# Sensor_Plug_PCB.net
KiCad netlist of a schematic drawn in EAGLE
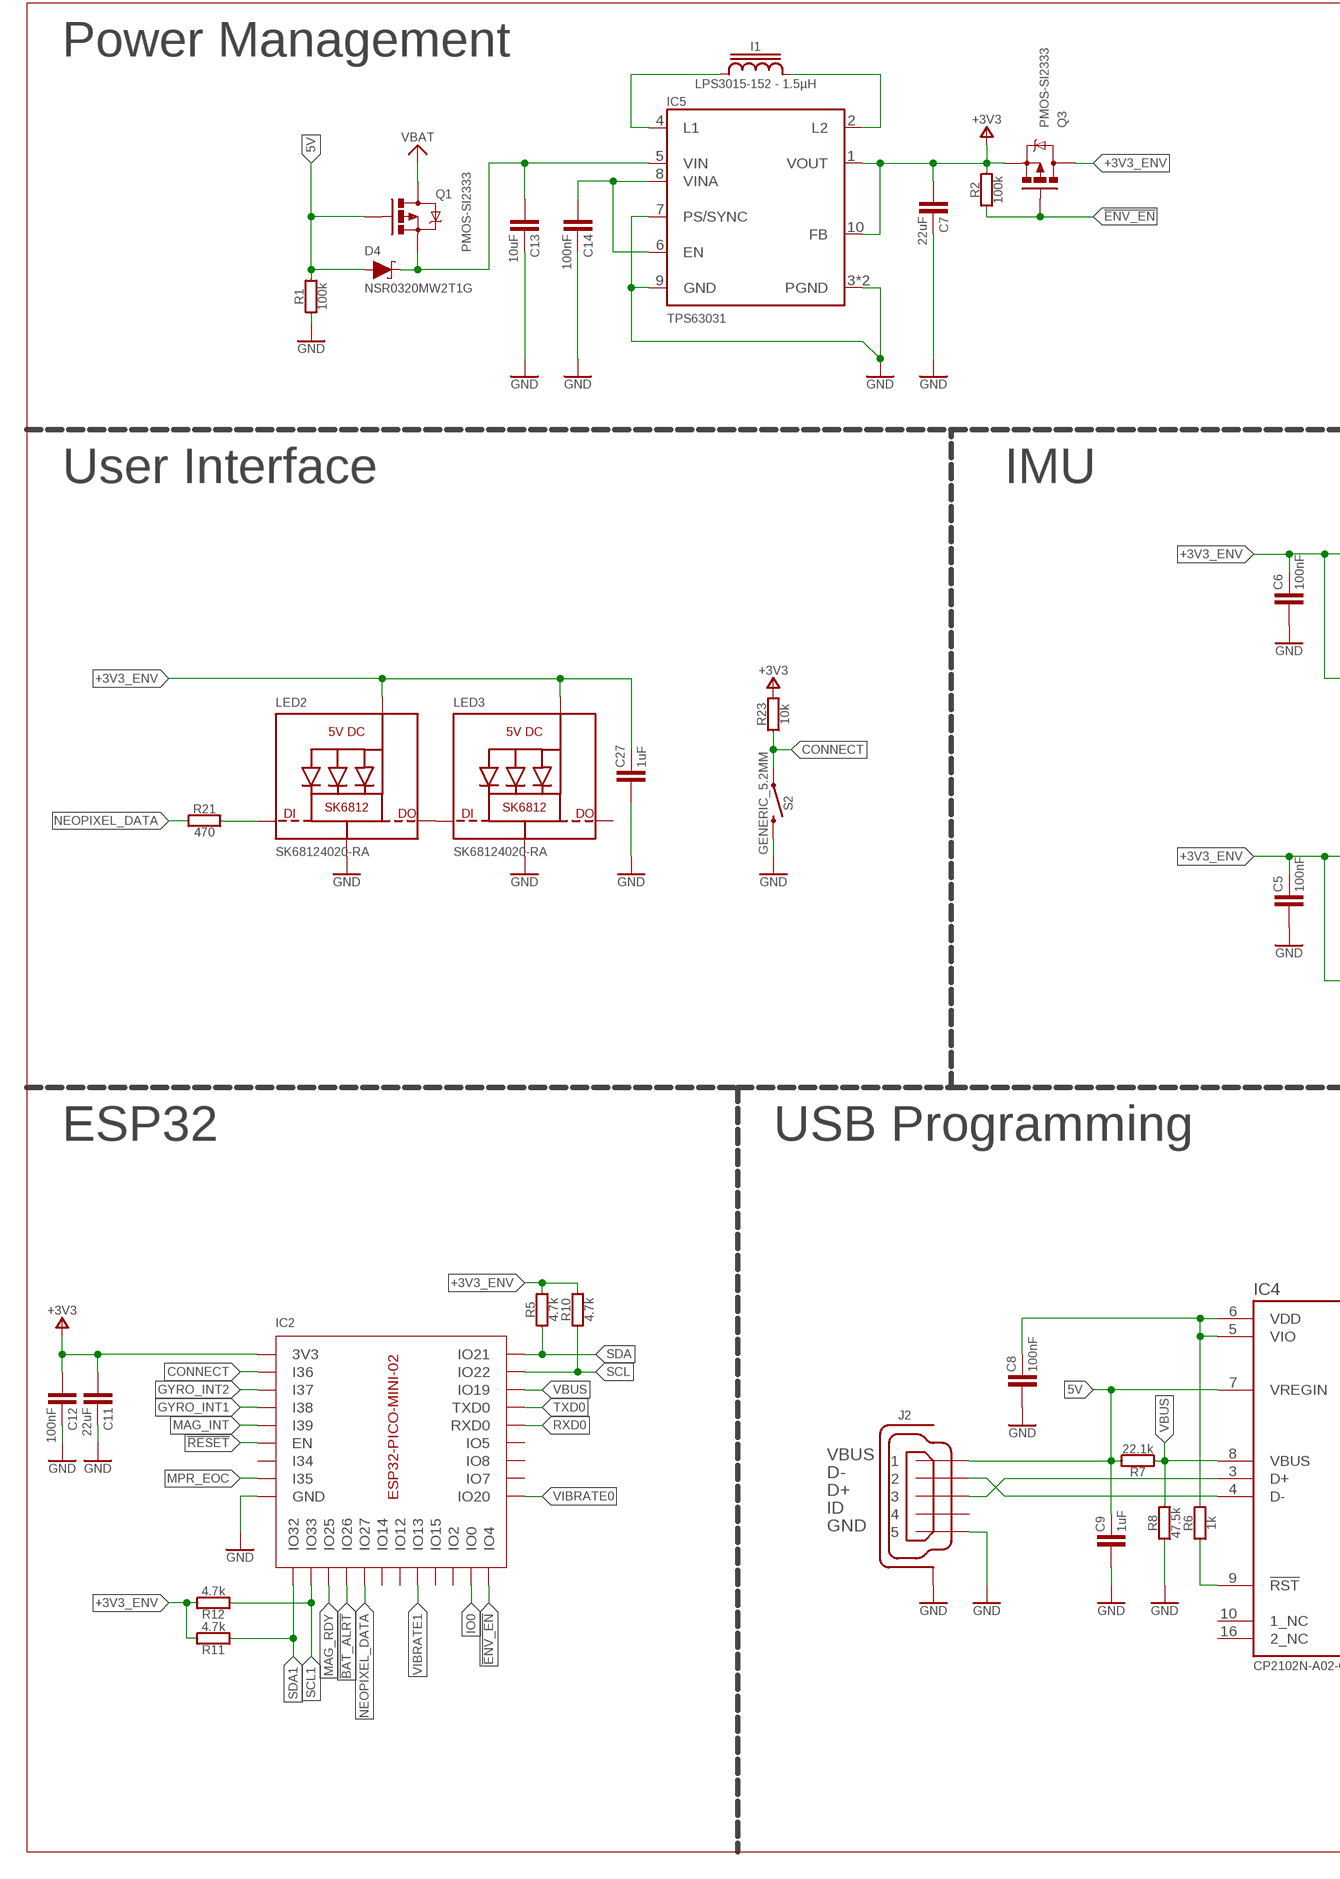
[diagram p0: schematic, sheet 1, part 1 of 2]
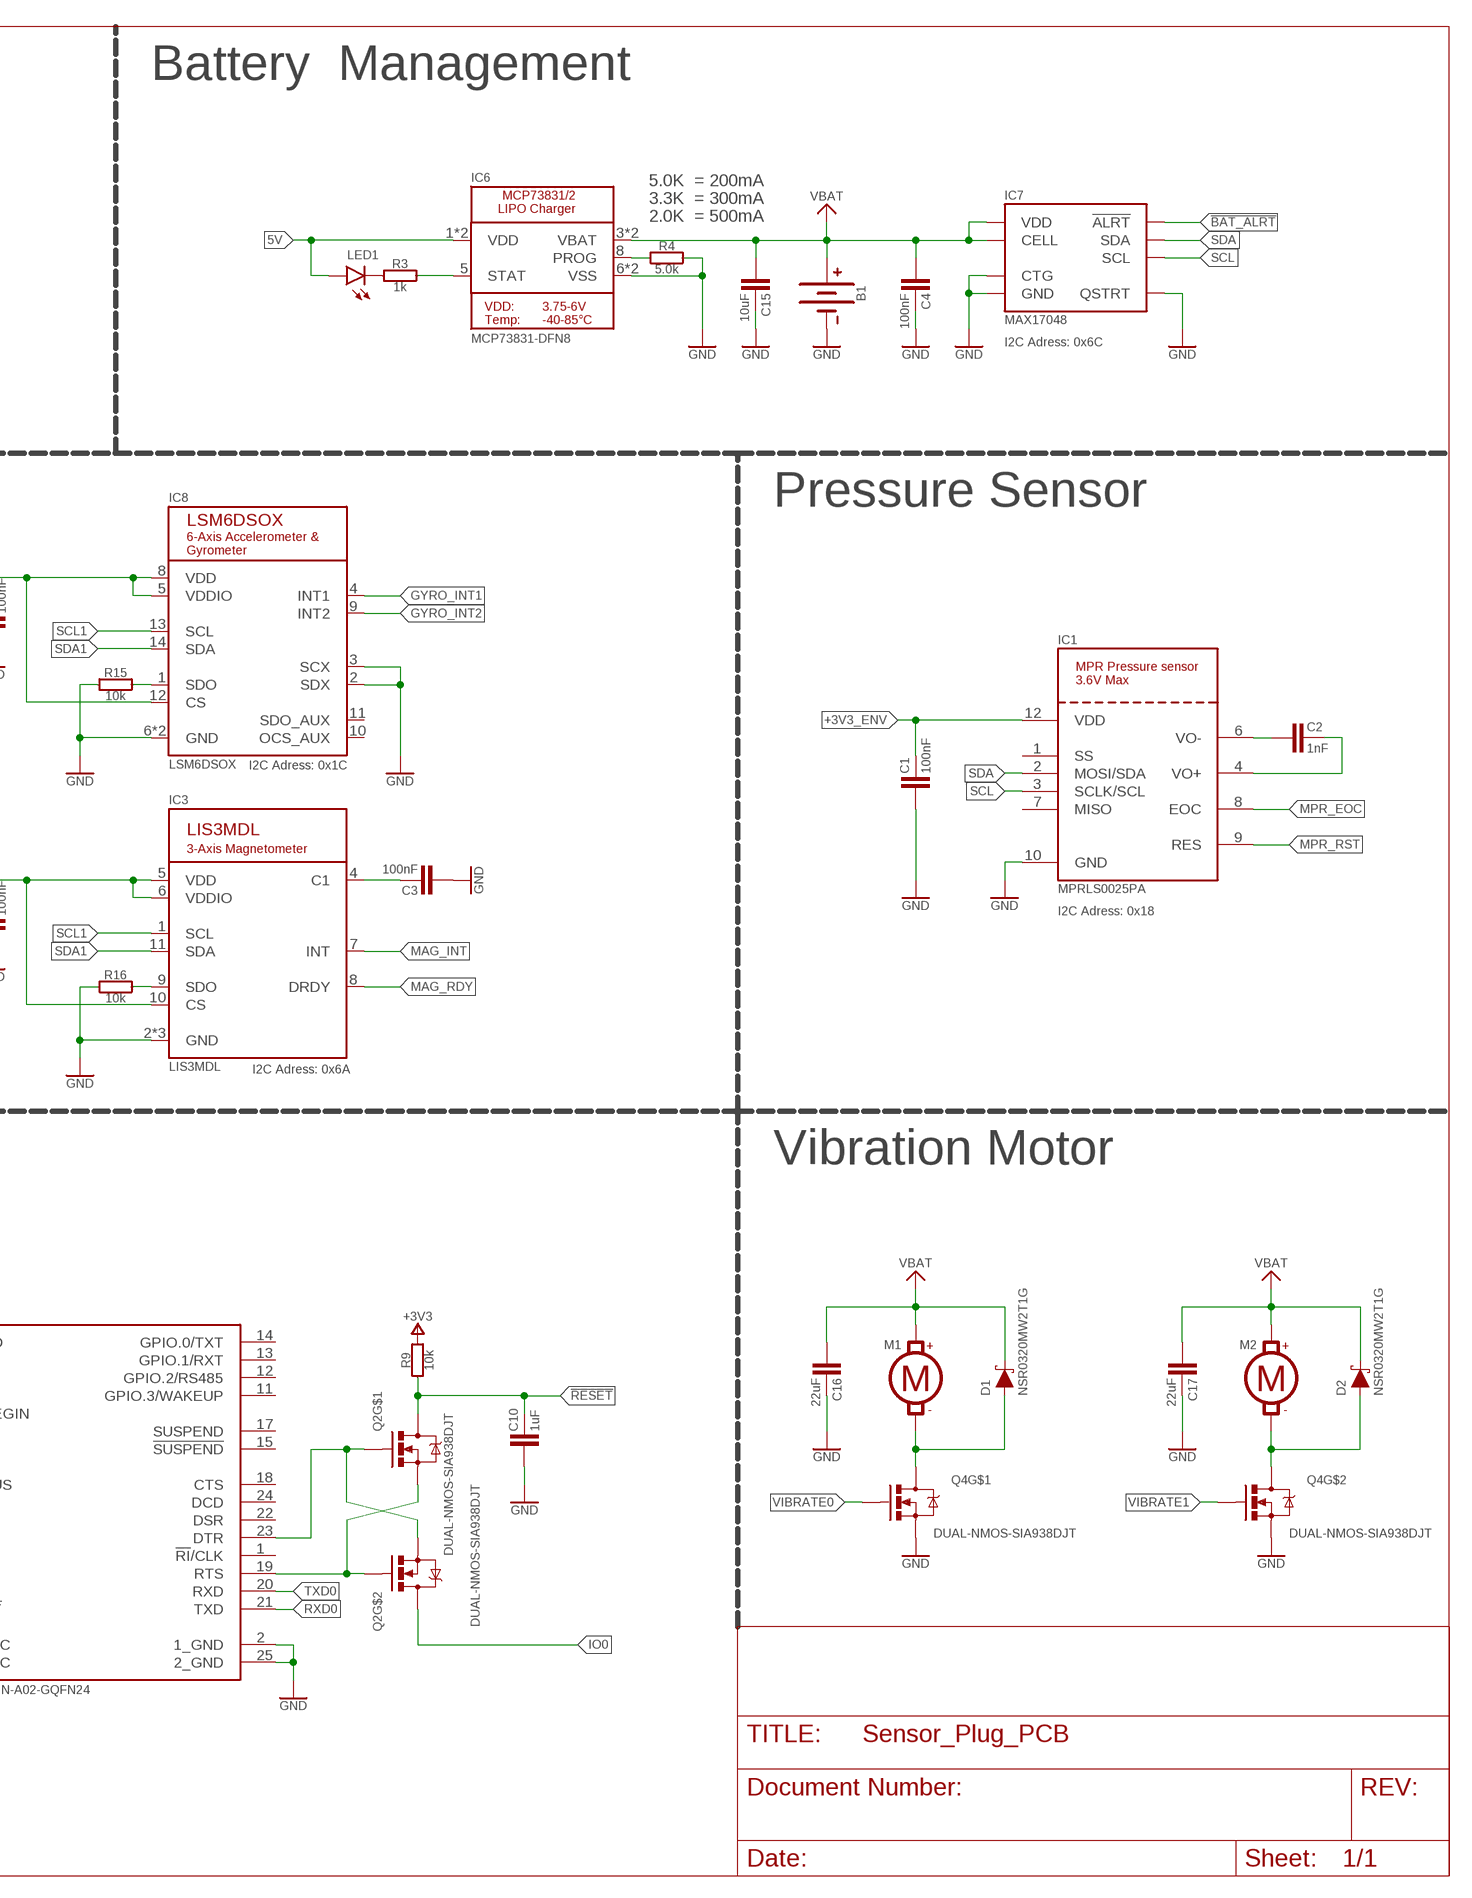
[diagram p1: schematic, sheet 1, part 2 of 2]

(export (version "E")
  (design (tool "Eeschema 10.0.6"))
  (components
    (comp (ref "B1")
      (value "LIPO-JST_PH_SMDV-02")
      (footprint "eagle-import:JST_PH_SMDV-02")
      (libsource (lib "eagle-import") (part "LIPO-JST_PH_SMDV-02"))
    )
    (comp (ref "C1")
      (value "100nF")
      (footprint "eagle-import:C0603")
      (libsource (lib "eagle-import") (part "C-0603"))
    )
    (comp (ref "C2")
      (value "1nF")
      (footprint "eagle-import:C0603")
      (libsource (lib "eagle-import") (part "C-0603"))
    )
    (comp (ref "C3")
      (value "100nF")
      (footprint "eagle-import:C0603")
      (libsource (lib "eagle-import") (part "C-0603"))
    )
    (comp (ref "C4")
      (value "100nF")
      (footprint "eagle-import:C0603")
      (libsource (lib "eagle-import") (part "C-0603"))
    )
    (comp (ref "C5")
      (value "100nF")
      (footprint "eagle-import:C0603")
      (libsource (lib "eagle-import") (part "C-0603"))
    )
    (comp (ref "C6")
      (value "100nF")
      (footprint "eagle-import:C0603")
      (libsource (lib "eagle-import") (part "C-0603"))
    )
    (comp (ref "C7")
      (value "22uF")
      (footprint "eagle-import:C0805")
      (libsource (lib "eagle-import") (part "C-0805"))
    )
    (comp (ref "C8")
      (value "100nF")
      (footprint "eagle-import:C0603")
      (libsource (lib "eagle-import") (part "C-0603"))
    )
    (comp (ref "C9")
      (value "1uF")
      (footprint "eagle-import:C0603")
      (libsource (lib "eagle-import") (part "C-0603"))
    )
    (comp (ref "C10")
      (value "1uF")
      (footprint "eagle-import:C0603")
      (libsource (lib "eagle-import") (part "C-0603"))
    )
    (comp (ref "C11")
      (value "22uF")
      (footprint "eagle-import:C0805")
      (libsource (lib "eagle-import") (part "C-0805"))
    )
    (comp (ref "C12")
      (value "100nF")
      (footprint "eagle-import:C0603")
      (libsource (lib "eagle-import") (part "C-0603"))
    )
    (comp (ref "C13")
      (value "10uF")
      (footprint "eagle-import:C0805")
      (libsource (lib "eagle-import") (part "C-0805"))
    )
    (comp (ref "C14")
      (value "100nF")
      (footprint "eagle-import:C0603")
      (libsource (lib "eagle-import") (part "C-0603"))
    )
    (comp (ref "C15")
      (value "10uF")
      (footprint "eagle-import:C0805")
      (libsource (lib "eagle-import") (part "C-0805"))
    )
    (comp (ref "C16")
      (value "22uF")
      (footprint "eagle-import:C0805")
      (libsource (lib "eagle-import") (part "C-0805"))
    )
    (comp (ref "C17")
      (value "22uF")
      (footprint "eagle-import:C0805")
      (libsource (lib "eagle-import") (part "C-0805"))
    )
    (comp (ref "C27")
      (value "1uF")
      (footprint "eagle-import:C0603")
      (libsource (lib "eagle-import") (part "C-0603"))
    )
    (comp (ref "D1")
      (value "NSR0320MW2T1G")
      (footprint "eagle-import:SOD-323")
      (libsource (lib "eagle-import") (part "DIODE-SCHOTTKY-SOD323"))
    )
    (comp (ref "D2")
      (value "NSR0320MW2T1G")
      (footprint "eagle-import:SOD-323")
      (libsource (lib "eagle-import") (part "DIODE-SCHOTTKY-SOD323"))
    )
    (comp (ref "D4")
      (value "NSR0320MW2T1G")
      (footprint "eagle-import:SOD-323")
      (libsource (lib "eagle-import") (part "DIODE-SCHOTTKY-SOD323"))
    )
    (comp (ref "I1")
      (value "LPS3015-152 - 1.5µH")
      (footprint "eagle-import:LPS3015")
      (libsource (lib "eagle-import") (part "I-LPS3015"))
    )
    (comp (ref "IC1")
      (value "MPRLS0025PA")
      (footprint "eagle-import:MPRLS0025PA")
      (fields (field (name "MPN") "MPRLS0025PA00001A"))
      (libsource (lib "eagle-import") (part "MPRLS0025PA"))
    )
    (comp (ref "IC2")
      (value "EPS32-PICO-MINI-02")
      (footprint "eagle-import:ESP32-PICO-MINI-02")
      (libsource (lib "eagle-import") (part "EPS32-PICO-MINI-02"))
    )
    (comp (ref "IC3")
      (value "LIS3MDL")
      (footprint "eagle-import:LGA12_2X2MM")
      (libsource (lib "eagle-import") (part "LIS3MDL"))
    )
    (comp (ref "IC4")
      (value "CP2102N-A02-GQFN24")
      (footprint "eagle-import:QFN24")
      (libsource (lib "eagle-import") (part "CP2102N-A02-GQFN24"))
    )
    (comp (ref "IC5")
      (value "TPS63031")
      (footprint "eagle-import:R-PWSON-N10")
      (libsource (lib "eagle-import") (part "TPS63031"))
    )
    (comp (ref "IC6")
      (value "MCP73831-DFN8")
      (footprint "eagle-import:DFN8_2X3")
      (libsource (lib "eagle-import") (part "MCP73831-DFN8"))
    )
    (comp (ref "IC7")
      (value "MAX17048")
      (footprint "eagle-import:DFN8_2X2")
      (libsource (lib "eagle-import") (part "MAX17048/9"))
    )
    (comp (ref "IC8")
      (value "LSM6DSOX")
      (footprint "eagle-import:LGA-14L")
      (libsource (lib "eagle-import") (part "LSM6DSOX"))
    )
    (comp (ref "J2")
      (value "-")
      (footprint "eagle-import:ZX62-AB-5PA")
      (fields (field (name "MPN") "ZX62-AB-5PA(31) "))
      (libsource (lib "eagle-import") (part "USB-MICROHIROSE"))
    )
    (comp (ref "LED1")
      (value "LED-0603-SIDEVIEW")
      (footprint "eagle-import:LED_0603_SIDEVIEW")
      (libsource (lib "eagle-import") (part "LED-0603-SIDEVIEW"))
    )
    (comp (ref "LED2")
      (value "SK68124020-RA")
      (footprint "eagle-import:SK6812-4020-SIDE")
      (fields (field (name "MPN") "SK6812 SIDE-A"))
      (libsource (lib "eagle-import") (part "SK68124020-RA"))
    )
    (comp (ref "LED3")
      (value "SK68124020-RA")
      (footprint "eagle-import:SK6812-4020-SIDE")
      (fields (field (name "MPN") "SK6812 SIDE-A"))
      (libsource (lib "eagle-import") (part "SK68124020-RA"))
    )
    (comp (ref "M1")
      (value "MOTOR-PADS")
      (footprint "eagle-import:MOTOR-PADS")
      (libsource (lib "eagle-import") (part "MOTOR-PADS"))
    )
    (comp (ref "M2")
      (value "MOTOR-PADS")
      (footprint "eagle-import:MOTOR-PADS")
      (libsource (lib "eagle-import") (part "MOTOR-PADS"))
    )
    (comp (ref "Q1")
      (value "PMOS-SI2333")
      (footprint "eagle-import:SOT23-3")
      (fields (field (name "MPN") "SI2333DDS-T1-GE3"))
      (libsource (lib "eagle-import") (part "PMOS-SI2333"))
    )
    (comp (ref "Q2")
      (value "DUAL-NMOS-SIA938DJT")
      (footprint "eagle-import:POWERPAK_SC70-6L_DUAL")
      (libsource (lib "eagle-import") (part "DUAL-NMOS-SIA938DJT"))
    )
    (comp (ref "Q3")
      (value "PMOS-SI2333")
      (footprint "eagle-import:SOT23-3")
      (fields (field (name "MPN") "SI2333DDS-T1-GE3"))
      (libsource (lib "eagle-import") (part "PMOS-SI2333"))
    )
    (comp (ref "Q4")
      (value "DUAL-NMOS-SIA938DJT")
      (footprint "eagle-import:POWERPAK_SC70-6L_DUAL")
      (libsource (lib "eagle-import") (part "DUAL-NMOS-SIA938DJT"))
    )
    (comp (ref "R1")
      (value "100k")
      (footprint "eagle-import:R0603")
      (libsource (lib "eagle-import") (part "R-0603"))
    )
    (comp (ref "R2")
      (value "100k")
      (footprint "eagle-import:R0603")
      (libsource (lib "eagle-import") (part "R-0603"))
    )
    (comp (ref "R3")
      (value "1k")
      (footprint "eagle-import:R0603")
      (libsource (lib "eagle-import") (part "R-0603"))
    )
    (comp (ref "R4")
      (value "5.0k")
      (footprint "eagle-import:R0603")
      (libsource (lib "eagle-import") (part "R-0603"))
    )
    (comp (ref "R5")
      (value "4.7k")
      (footprint "eagle-import:R0603")
      (libsource (lib "eagle-import") (part "R-0603"))
    )
    (comp (ref "R6")
      (value "1k")
      (footprint "eagle-import:R0603")
      (libsource (lib "eagle-import") (part "R-0603"))
    )
    (comp (ref "R7")
      (value "22.1k")
      (footprint "eagle-import:R0603")
      (libsource (lib "eagle-import") (part "R-0603"))
    )
    (comp (ref "R8")
      (value "47.5k")
      (footprint "eagle-import:R0603")
      (libsource (lib "eagle-import") (part "R-0603"))
    )
    (comp (ref "R9")
      (value "10k")
      (footprint "eagle-import:R0603")
      (libsource (lib "eagle-import") (part "R-0603"))
    )
    (comp (ref "R10")
      (value "4.7k")
      (footprint "eagle-import:R0603")
      (libsource (lib "eagle-import") (part "R-0603"))
    )
    (comp (ref "R11")
      (value "4.7k")
      (footprint "eagle-import:R0603")
      (libsource (lib "eagle-import") (part "R-0603"))
    )
    (comp (ref "R12")
      (value "4.7k")
      (footprint "eagle-import:R0603")
      (libsource (lib "eagle-import") (part "R-0603"))
    )
    (comp (ref "R15")
      (value "10k")
      (footprint "eagle-import:R0603")
      (libsource (lib "eagle-import") (part "R-0603"))
    )
    (comp (ref "R16")
      (value "10k")
      (footprint "eagle-import:R0603")
      (libsource (lib "eagle-import") (part "R-0603"))
    )
    (comp (ref "R21")
      (value "470")
      (footprint "eagle-import:R0603")
      (libsource (lib "eagle-import") (part "R-0603"))
    )
    (comp (ref "R23")
      (value "10k")
      (footprint "eagle-import:R0603")
      (libsource (lib "eagle-import") (part "R-0603"))
    )
    (comp (ref "S2")
      (value "GENERIC_5.2MM")
      (footprint "eagle-import:C&K_KMS")
      (libsource (lib "eagle-import") (part "TACT_SWITCHC&K_KMS221GLFS"))
    )
  )
  (nets
    (net (code "1") (name "+3V3") (class "Default")
      (node (ref "C11") (pin "2") (pinfunction "2_2") (pintype "passive"))
      (node (ref "C12") (pin "2") (pinfunction "2_2") (pintype "passive"))
      (node (ref "C7") (pin "2") (pinfunction "2_2") (pintype "passive"))
      (node (ref "IC2") (pin "P$3") (pinfunction "3V3_P$3") (pintype "bidirectional"))
      (node (ref "IC5") (pin "1") (pinfunction "VOUT_1") (pintype "passive"))
      (node (ref "IC5") (pin "10") (pinfunction "FB_10") (pintype "passive"))
      (node (ref "Q3") (pin "2") (pinfunction "S_2") (pintype "passive"))
      (node (ref "R2") (pin "2") (pinfunction "2_2") (pintype "passive"))
      (node (ref "R23") (pin "2") (pinfunction "2_2") (pintype "passive"))
      (node (ref "R9") (pin "2") (pinfunction "2_2") (pintype "passive"))
    )
    (net (code "2") (name "+3V3_ENV") (class "Default")
      (node (ref "C1") (pin "1") (pinfunction "1_1") (pintype "passive"))
      (node (ref "C27") (pin "1") (pinfunction "1_1") (pintype "passive"))
      (node (ref "C5") (pin "1") (pinfunction "1_1") (pintype "passive"))
      (node (ref "C6") (pin "1") (pinfunction "1_1") (pintype "passive"))
      (node (ref "IC1") (pin "12") (pinfunction "VDD_12") (pintype "bidirectional"))
      (node (ref "IC3") (pin "10") (pinfunction "CS_10") (pintype "input"))
      (node (ref "IC3") (pin "5") (pinfunction "VDD_5") (pintype "power_in"))
      (node (ref "IC3") (pin "6") (pinfunction "VDDIO_6") (pintype "power_in"))
      (node (ref "IC8") (pin "12") (pinfunction "CS_12") (pintype "bidirectional"))
      (node (ref "IC8") (pin "5") (pinfunction "VDDIO_5") (pintype "power_in"))
      (node (ref "IC8") (pin "8") (pinfunction "VDD_8") (pintype "power_in"))
      (node (ref "LED2") (pin "VDD") (pinfunction "VDD_VDD") (pintype "power_in"))
      (node (ref "LED3") (pin "VDD") (pinfunction "VDD_VDD") (pintype "power_in"))
      (node (ref "Q3") (pin "3") (pinfunction "D_3") (pintype "passive"))
      (node (ref "R10") (pin "2") (pinfunction "2_2") (pintype "passive"))
      (node (ref "R11") (pin "2") (pinfunction "2_2") (pintype "passive"))
      (node (ref "R12") (pin "2") (pinfunction "2_2") (pintype "passive"))
      (node (ref "R5") (pin "2") (pinfunction "2_2") (pintype "passive"))
    )
    (net (code "3") (name "/~{BAT_ALRT}") (class "Default")
      (node (ref "IC2") (pin "P$16") (pinfunction "IO26_P$16") (pintype "bidirectional"))
      (node (ref "IC7") (pin "5") (pinfunction "~{ALRT}_5") (pintype "bidirectional"))
    )
    (net (code "4") (name "/~{ENV_EN}") (class "Default")
      (node (ref "IC2") (pin "P$24") (pinfunction "IO4_P$24") (pintype "bidirectional"))
      (node (ref "Q3") (pin "1") (pinfunction "G_1") (pintype "passive"))
      (node (ref "R2") (pin "1") (pinfunction "1_1") (pintype "passive"))
    )
    (net (code "5") (name "/~{RESET}") (class "Default")
      (node (ref "C10") (pin "1") (pinfunction "1_1") (pintype "passive"))
      (node (ref "IC2") (pin "P$8") (pinfunction "EN_P$8") (pintype "bidirectional"))
      (node (ref "Q2") (pin "6") (pinfunction "D_6") (pintype "passive"))
      (node (ref "Q2") (pin "7") (pinfunction "D_7") (pintype "passive"))
      (node (ref "R9") (pin "1") (pinfunction "1_1") (pintype "passive"))
    )
    (net (code "6") (name "5V") (class "Default")
      (node (ref "C9") (pin "1") (pinfunction "1_1") (pintype "passive"))
      (node (ref "D4") (pin "A") (pinfunction "A_A") (pintype "passive"))
      (node (ref "IC4") (pin "7") (pinfunction "VREGIN_7") (pintype "power_in"))
      (node (ref "IC6") (pin "1") (pinfunction "VDD_1") (pintype "power_in"))
      (node (ref "IC6") (pin "2") (pinfunction "VDD_2") (pintype "power_in"))
      (node (ref "J2") (pin "1") (pinfunction "1_1") (pintype "passive"))
      (node (ref "LED1") (pin "A") (pinfunction "A_A") (pintype "passive"))
      (node (ref "Q1") (pin "1") (pinfunction "G_1") (pintype "passive"))
      (node (ref "R1") (pin "2") (pinfunction "2_2") (pintype "passive"))
      (node (ref "R7") (pin "2") (pinfunction "2_2") (pintype "passive"))
    )
    (net (code "7") (name "CONNECT") (class "Default")
      (node (ref "IC2") (pin "P$4") (pinfunction "I36_P$4") (pintype "bidirectional"))
      (node (ref "R23") (pin "1") (pinfunction "1_1") (pintype "passive"))
      (node (ref "S2") (pin "1") (pinfunction "1_1") (pintype "passive"))
      (node (ref "S2") (pin "5") (pinfunction "1_5") (pintype "passive"))
    )
    (net (code "8") (name "GND") (class "Default")
      (node (ref "B1") (pin "1") (pinfunction "-_1") (pintype "power_in"))
      (node (ref "C1") (pin "2") (pinfunction "2_2") (pintype "passive"))
      (node (ref "C10") (pin "2") (pinfunction "2_2") (pintype "passive"))
      (node (ref "C11") (pin "1") (pinfunction "1_1") (pintype "passive"))
      (node (ref "C12") (pin "1") (pinfunction "1_1") (pintype "passive"))
      (node (ref "C13") (pin "1") (pinfunction "1_1") (pintype "passive"))
      (node (ref "C14") (pin "1") (pinfunction "1_1") (pintype "passive"))
      (node (ref "C15") (pin "1") (pinfunction "1_1") (pintype "passive"))
      (node (ref "C16") (pin "1") (pinfunction "1_1") (pintype "passive"))
      (node (ref "C17") (pin "1") (pinfunction "1_1") (pintype "passive"))
      (node (ref "C27") (pin "2") (pinfunction "2_2") (pintype "passive"))
      (node (ref "C3") (pin "2") (pinfunction "2_2") (pintype "passive"))
      (node (ref "C4") (pin "1") (pinfunction "1_1") (pintype "passive"))
      (node (ref "C5") (pin "2") (pinfunction "2_2") (pintype "passive"))
      (node (ref "C6") (pin "2") (pinfunction "2_2") (pintype "passive"))
      (node (ref "C7") (pin "1") (pinfunction "1_1") (pintype "passive"))
      (node (ref "C8") (pin "2") (pinfunction "2_2") (pintype "passive"))
      (node (ref "C9") (pin "2") (pinfunction "2_2") (pintype "passive"))
      (node (ref "IC1") (pin "10") (pinfunction "GND_10") (pintype "bidirectional"))
      (node (ref "IC2") (pin "P$1") (pinfunction "GND_P$1") (pintype "bidirectional"))
      (node (ref "IC2") (pin "P$11") (pinfunction "GND_P$11") (pintype "bidirectional"))
      (node (ref "IC2") (pin "P$14") (pinfunction "GND_P$14") (pintype "bidirectional"))
      (node (ref "IC2") (pin "P$2") (pinfunction "GND_P$2") (pintype "bidirectional"))
      (node (ref "IC2") (pin "P$36") (pinfunction "GND_P$36") (pintype "bidirectional"))
      (node (ref "IC2") (pin "P$37") (pinfunction "GND_P$37") (pintype "bidirectional"))
      (node (ref "IC2") (pin "P$38") (pinfunction "GND_P$38") (pintype "bidirectional"))
      (node (ref "IC2") (pin "P$39") (pinfunction "GND_P$39") (pintype "bidirectional"))
      (node (ref "IC2") (pin "P$40") (pinfunction "GND_P$40") (pintype "bidirectional"))
      (node (ref "IC2") (pin "P$41") (pinfunction "GND_P$41") (pintype "bidirectional"))
      (node (ref "IC2") (pin "P$42") (pinfunction "GND_P$42") (pintype "bidirectional"))
      (node (ref "IC2") (pin "P$43") (pinfunction "GND_P$43") (pintype "bidirectional"))
      (node (ref "IC2") (pin "P$44") (pinfunction "GND_P$44") (pintype "bidirectional"))
      (node (ref "IC2") (pin "P$45") (pinfunction "GND_P$45") (pintype "bidirectional"))
      (node (ref "IC2") (pin "P$46") (pinfunction "GND_P$46") (pintype "bidirectional"))
      (node (ref "IC2") (pin "P$47") (pinfunction "GND_P$47") (pintype "bidirectional"))
      (node (ref "IC2") (pin "P$48") (pinfunction "GND_P$48") (pintype "bidirectional"))
      (node (ref "IC2") (pin "P$49") (pinfunction "GND_P$49") (pintype "bidirectional"))
      (node (ref "IC2") (pin "P$50") (pinfunction "GND_P$50") (pintype "bidirectional"))
      (node (ref "IC2") (pin "P$51") (pinfunction "GND_P$51") (pintype "bidirectional"))
      (node (ref "IC2") (pin "P$52") (pinfunction "GND_P$52") (pintype "bidirectional"))
      (node (ref "IC2") (pin "P$53") (pinfunction "GND_P$53") (pintype "bidirectional"))
      (node (ref "IC2") (pin "P$54") (pinfunction "GND_P$54") (pintype "bidirectional"))
      (node (ref "IC2") (pin "P$55") (pinfunction "GND_P$55") (pintype "bidirectional"))
      (node (ref "IC2") (pin "P$56") (pinfunction "GND_P$56") (pintype "bidirectional"))
      (node (ref "IC2") (pin "P$57") (pinfunction "GND_P$57") (pintype "bidirectional"))
      (node (ref "IC2") (pin "P$58") (pinfunction "GND_P$58") (pintype "bidirectional"))
      (node (ref "IC2") (pin "P$59") (pinfunction "GND_P$59") (pintype "bidirectional"))
      (node (ref "IC2") (pin "P$60") (pinfunction "GND_P$60") (pintype "bidirectional"))
      (node (ref "IC2") (pin "P$61") (pinfunction "GND_P$61") (pintype "bidirectional"))
      (node (ref "IC3") (pin "12") (pinfunction "GND_12") (pintype "power_in"))
      (node (ref "IC3") (pin "2") (pinfunction "GND_2") (pintype "power_in"))
      (node (ref "IC3") (pin "3") (pinfunction "GND_3") (pintype "power_in"))
      (node (ref "IC4") (pin "2") (pinfunction "1_GND_2") (pintype "power_in"))
      (node (ref "IC4") (pin "25") (pinfunction "2_GND_25") (pintype "power_in"))
      (node (ref "IC5") (pin "11") (pinfunction "PGND_11") (pintype "power_in"))
      (node (ref "IC5") (pin "3") (pinfunction "PGND_3") (pintype "power_in"))
      (node (ref "IC5") (pin "7") (pinfunction "PS/SYNC_7") (pintype "input"))
      (node (ref "IC5") (pin "9") (pinfunction "GND_9") (pintype "power_in"))
      (node (ref "IC6") (pin "6") (pinfunction "VSS_6") (pintype "power_in"))
      (node (ref "IC6") (pin "9") (pinfunction "VSS_9") (pintype "power_in"))
      (node (ref "IC7") (pin "1") (pinfunction "CTG_1") (pintype "input"))
      (node (ref "IC7") (pin "4") (pinfunction "GND_4") (pintype "bidirectional"))
      (node (ref "IC7") (pin "6") (pinfunction "QSTRT_6") (pintype "bidirectional"))
      (node (ref "IC7") (pin "9") (pinfunction "GND_9") (pintype "bidirectional"))
      (node (ref "IC8") (pin "2") (pinfunction "SDX_2") (pintype "bidirectional"))
      (node (ref "IC8") (pin "3") (pinfunction "SCX_3") (pintype "bidirectional"))
      (node (ref "IC8") (pin "6") (pinfunction "GND_6") (pintype "power_in"))
      (node (ref "IC8") (pin "7") (pinfunction "GND_7") (pintype "power_in"))
      (node (ref "J2") (pin "10") (pinfunction "SH_10") (pintype "passive"))
      (node (ref "J2") (pin "11") (pinfunction "SH_11") (pintype "passive"))
      (node (ref "J2") (pin "5") (pinfunction "5_5") (pintype "passive"))
      (node (ref "J2") (pin "6") (pinfunction "SH_6") (pintype "passive"))
      (node (ref "J2") (pin "7") (pinfunction "SH_7") (pintype "passive"))
      (node (ref "J2") (pin "8") (pinfunction "SH_8") (pintype "passive"))
      (node (ref "J2") (pin "9") (pinfunction "SH_9") (pintype "passive"))
      (node (ref "LED2") (pin "GND") (pinfunction "GND_GND") (pintype "power_in"))
      (node (ref "LED3") (pin "GND") (pinfunction "GND_GND") (pintype "power_in"))
      (node (ref "Q4") (pin "1") (pinfunction "S_1") (pintype "passive"))
      (node (ref "Q4") (pin "4") (pinfunction "S_4") (pintype "passive"))
      (node (ref "R1") (pin "1") (pinfunction "1_1") (pintype "passive"))
      (node (ref "R15") (pin "1") (pinfunction "1_1") (pintype "passive"))
      (node (ref "R16") (pin "1") (pinfunction "1_1") (pintype "passive"))
      (node (ref "R4") (pin "2") (pinfunction "2_2") (pintype "passive"))
      (node (ref "R8") (pin "1") (pinfunction "1_1") (pintype "passive"))
      (node (ref "S2") (pin "2") (pinfunction "2_2") (pintype "passive"))
      (node (ref "S2") (pin "3") (pinfunction "2_3") (pintype "passive"))
      (node (ref "S2") (pin "4") (pinfunction "2_4") (pintype "passive"))
    )
    (net (code "9") (name "GYRO_INT1") (class "Default")
      (node (ref "IC2") (pin "P$6") (pinfunction "I38_P$6") (pintype "bidirectional"))
      (node (ref "IC8") (pin "4") (pinfunction "INT1_4") (pintype "bidirectional"))
    )
    (net (code "10") (name "GYRO_INT2") (class "Default")
      (node (ref "IC2") (pin "P$5") (pinfunction "I37_P$5") (pintype "bidirectional"))
      (node (ref "IC8") (pin "9") (pinfunction "INT2_9") (pintype "bidirectional"))
    )
    (net (code "11") (name "IO0") (class "Default")
      (node (ref "IC2") (pin "P$23") (pinfunction "IO0_P$23") (pintype "bidirectional"))
      (node (ref "Q2") (pin "3") (pinfunction "D_3") (pintype "passive"))
      (node (ref "Q2") (pin "8") (pinfunction "D_8") (pintype "passive"))
    )
    (net (code "12") (name "MAG_INT") (class "Default")
      (node (ref "IC2") (pin "P$7") (pinfunction "I39_P$7") (pintype "bidirectional"))
      (node (ref "IC3") (pin "7") (pinfunction "INT_7") (pintype "output"))
    )
    (net (code "13") (name "MAG_RDY") (class "Default")
      (node (ref "IC2") (pin "P$15") (pinfunction "IO25_P$15") (pintype "bidirectional"))
      (node (ref "IC3") (pin "8") (pinfunction "DRDY_8") (pintype "output"))
    )
    (net (code "14") (name "MPR_EOC") (class "Default")
      (node (ref "IC1") (pin "8") (pinfunction "EOC_8") (pintype "bidirectional"))
      (node (ref "IC2") (pin "P$10") (pinfunction "I35_P$10") (pintype "bidirectional"))
    )
    (net (code "15") (name "MPR_RST") (class "Default")
      (node (ref "IC1") (pin "9") (pinfunction "RES_9") (pintype "bidirectional"))
    )
    (net (code "16") (name "NEOPIXEL_DATA") (class "Default")
      (node (ref "IC2") (pin "P$17") (pinfunction "IO27_P$17") (pintype "bidirectional"))
      (node (ref "R21") (pin "2") (pinfunction "2_2") (pintype "passive"))
    )
    (net (code "17") (name "Net-(D1-PadA)") (class "Default")
      (node (ref "D1") (pin "A") (pinfunction "A_A") (pintype "passive"))
      (node (ref "M1") (pin "N") (pinfunction "N_N") (pintype "bidirectional"))
      (node (ref "Q4") (pin "6") (pinfunction "D_6") (pintype "passive"))
      (node (ref "Q4") (pin "7") (pinfunction "D_7") (pintype "passive"))
    )
    (net (code "18") (name "Net-(D2-PadA)") (class "Default")
      (node (ref "D2") (pin "A") (pinfunction "A_A") (pintype "passive"))
      (node (ref "M2") (pin "N") (pinfunction "N_N") (pintype "bidirectional"))
      (node (ref "Q4") (pin "3") (pinfunction "D_3") (pintype "passive"))
      (node (ref "Q4") (pin "8") (pinfunction "D_8") (pintype "passive"))
    )
    (net (code "19") (name "Net-(IC1-VO+)") (class "Default")
      (node (ref "C2") (pin "1") (pinfunction "1_1") (pintype "passive"))
      (node (ref "IC1") (pin "4") (pinfunction "VO+_4") (pintype "bidirectional"))
    )
    (net (code "20") (name "Net-(IC1-VO-)") (class "Default")
      (node (ref "C2") (pin "2") (pinfunction "2_2") (pintype "passive"))
      (node (ref "IC1") (pin "6") (pinfunction "VO-_6") (pintype "bidirectional"))
    )
    (net (code "21") (name "Net-(IC3-C1)") (class "Default")
      (node (ref "C3") (pin "1") (pinfunction "1_1") (pintype "passive"))
      (node (ref "IC3") (pin "4") (pinfunction "C1_4") (pintype "input"))
    )
    (net (code "22") (name "Net-(IC3-SDO)") (class "Default")
      (node (ref "IC3") (pin "9") (pinfunction "SDO_9") (pintype "bidirectional"))
      (node (ref "R16") (pin "2") (pinfunction "2_2") (pintype "passive"))
    )
    (net (code "23") (name "Net-(IC4-D+)") (class "Default")
      (node (ref "IC4") (pin "3") (pinfunction "D+_3") (pintype "passive"))
      (node (ref "J2") (pin "3") (pinfunction "3_3") (pintype "passive"))
    )
    (net (code "24") (name "Net-(IC4-D-)") (class "Default")
      (node (ref "IC4") (pin "4") (pinfunction "D-_4") (pintype "passive"))
      (node (ref "J2") (pin "2") (pinfunction "2_2") (pintype "passive"))
    )
    (net (code "25") (name "Net-(IC4-DTR)") (class "Default")
      (node (ref "IC4") (pin "23") (pinfunction "DTR_23") (pintype "output"))
      (node (ref "Q2") (pin "2") (pinfunction "G_2") (pintype "passive"))
      (node (ref "Q2") (pin "4") (pinfunction "S_4") (pintype "passive"))
    )
    (net (code "26") (name "Net-(IC4-RTS)") (class "Default")
      (node (ref "IC4") (pin "19") (pinfunction "RTS_19") (pintype "output"))
      (node (ref "Q2") (pin "1") (pinfunction "S_1") (pintype "passive"))
      (node (ref "Q2") (pin "5") (pinfunction "G_5") (pintype "passive"))
    )
    (net (code "27") (name "Net-(IC4-VDD)") (class "Default")
      (node (ref "C8") (pin "1") (pinfunction "1_1") (pintype "passive"))
      (node (ref "IC4") (pin "5") (pinfunction "VIO_5") (pintype "power_in"))
      (node (ref "IC4") (pin "6") (pinfunction "VDD_6") (pintype "power_in"))
      (node (ref "R6") (pin "2") (pinfunction "2_2") (pintype "passive"))
    )
    (net (code "28") (name "Net-(IC4-~{RST})") (class "Default")
      (node (ref "IC4") (pin "9") (pinfunction "~{RST}_9") (pintype "input"))
      (node (ref "R6") (pin "1") (pinfunction "1_1") (pintype "passive"))
    )
    (net (code "29") (name "Net-(IC5-EN)") (class "Default")
      (node (ref "C14") (pin "2") (pinfunction "2_2") (pintype "passive"))
      (node (ref "IC5") (pin "6") (pinfunction "EN_6") (pintype "input"))
      (node (ref "IC5") (pin "8") (pinfunction "VINA_8") (pintype "passive"))
    )
    (net (code "30") (name "Net-(IC5-L1)") (class "Default")
      (node (ref "I1") (pin "1") (pinfunction "1_1") (pintype "passive"))
      (node (ref "IC5") (pin "4") (pinfunction "L1_4") (pintype "passive"))
    )
    (net (code "31") (name "Net-(IC5-L2)") (class "Default")
      (node (ref "I1") (pin "2") (pinfunction "2_2") (pintype "passive"))
      (node (ref "IC5") (pin "2") (pinfunction "L2_2") (pintype "passive"))
    )
    (net (code "32") (name "Net-(IC5-VIN)") (class "Default")
      (node (ref "C13") (pin "2") (pinfunction "2_2") (pintype "passive"))
      (node (ref "D4") (pin "C") (pinfunction "C_C") (pintype "passive"))
      (node (ref "IC5") (pin "5") (pinfunction "VIN_5") (pintype "power_in"))
      (node (ref "Q1") (pin "2") (pinfunction "S_2") (pintype "passive"))
    )
    (net (code "33") (name "Net-(IC6-PROG)") (class "Default")
      (node (ref "IC6") (pin "8") (pinfunction "PROG_8") (pintype "input"))
      (node (ref "R4") (pin "1") (pinfunction "1_1") (pintype "passive"))
    )
    (net (code "34") (name "Net-(IC6-STAT)") (class "Default")
      (node (ref "IC6") (pin "5") (pinfunction "STAT_5") (pintype "output"))
      (node (ref "R3") (pin "2") (pinfunction "2_2") (pintype "passive"))
    )
    (net (code "35") (name "Net-(IC8-SDO)") (class "Default")
      (node (ref "IC8") (pin "1") (pinfunction "SDO_1") (pintype "bidirectional"))
      (node (ref "R15") (pin "2") (pinfunction "2_2") (pintype "passive"))
    )
    (net (code "36") (name "Net-(LED1-PadC)") (class "Default")
      (node (ref "LED1") (pin "C") (pinfunction "C_C") (pintype "passive"))
      (node (ref "R3") (pin "1") (pinfunction "1_1") (pintype "passive"))
    )
    (net (code "37") (name "Net-(LED2-DI)") (class "Default")
      (node (ref "LED2") (pin "DIN") (pinfunction "DI_DIN") (pintype "input"))
      (node (ref "R21") (pin "1") (pinfunction "1_1") (pintype "passive"))
    )
    (net (code "38") (name "Net-(LED2-DO)") (class "Default")
      (node (ref "LED2") (pin "DOUT") (pinfunction "DO_DOUT") (pintype "output"))
      (node (ref "LED3") (pin "DIN") (pinfunction "DI_DIN") (pintype "input"))
    )
    (net (code "39") (name "RXD0") (class "Default")
      (node (ref "IC2") (pin "P$30") (pinfunction "RXD0_P$30") (pintype "bidirectional"))
      (node (ref "IC4") (pin "21") (pinfunction "TXD_21") (pintype "output"))
    )
    (net (code "40") (name "SCL") (class "Default")
      (node (ref "IC1") (pin "3") (pinfunction "SCLK/SCL_3") (pintype "bidirectional"))
      (node (ref "IC2") (pin "P$34") (pinfunction "IO22_P$34") (pintype "bidirectional"))
      (node (ref "IC7") (pin "7") (pinfunction "SCL_7") (pintype "output"))
      (node (ref "R10") (pin "1") (pinfunction "1_1") (pintype "passive"))
    )
    (net (code "41") (name "SCL1") (class "Default")
      (node (ref "IC2") (pin "P$13") (pinfunction "IO33_P$13") (pintype "bidirectional"))
      (node (ref "IC3") (pin "1") (pinfunction "SCL_1") (pintype "input"))
      (node (ref "IC8") (pin "13") (pinfunction "SCL_13") (pintype "bidirectional"))
      (node (ref "R12") (pin "1") (pinfunction "1_1") (pintype "passive"))
    )
    (net (code "42") (name "SDA") (class "Default")
      (node (ref "IC1") (pin "2") (pinfunction "MOSI/SDA_2") (pintype "bidirectional"))
      (node (ref "IC2") (pin "P$35") (pinfunction "IO21_P$35") (pintype "bidirectional"))
      (node (ref "IC7") (pin "8") (pinfunction "SDA_8") (pintype "input"))
      (node (ref "R5") (pin "1") (pinfunction "1_1") (pintype "passive"))
    )
    (net (code "43") (name "SDA1") (class "Default")
      (node (ref "IC2") (pin "P$12") (pinfunction "IO32_P$12") (pintype "bidirectional"))
      (node (ref "IC3") (pin "11") (pinfunction "SDA_11") (pintype "bidirectional"))
      (node (ref "IC8") (pin "14") (pinfunction "SDA_14") (pintype "bidirectional"))
      (node (ref "R11") (pin "1") (pinfunction "1_1") (pintype "passive"))
    )
    (net (code "44") (name "TXD0") (class "Default")
      (node (ref "IC2") (pin "P$31") (pinfunction "TXD0_P$31") (pintype "bidirectional"))
      (node (ref "IC4") (pin "20") (pinfunction "RXD_20") (pintype "input"))
    )
    (net (code "45") (name "VBAT") (class "Default")
      (node (ref "B1") (pin "2") (pinfunction "+_2") (pintype "power_in"))
      (node (ref "C15") (pin "2") (pinfunction "2_2") (pintype "passive"))
      (node (ref "C16") (pin "2") (pinfunction "2_2") (pintype "passive"))
      (node (ref "C17") (pin "2") (pinfunction "2_2") (pintype "passive"))
      (node (ref "C4") (pin "2") (pinfunction "2_2") (pintype "passive"))
      (node (ref "D1") (pin "C") (pinfunction "C_C") (pintype "passive"))
      (node (ref "D2") (pin "C") (pinfunction "C_C") (pintype "passive"))
      (node (ref "IC6") (pin "3") (pinfunction "VBAT_3") (pintype "power_in"))
      (node (ref "IC6") (pin "4") (pinfunction "VBAT_4") (pintype "power_in"))
      (node (ref "IC7") (pin "2") (pinfunction "CELL_2") (pintype "input"))
      (node (ref "IC7") (pin "3") (pinfunction "VDD_3") (pintype "bidirectional"))
      (node (ref "M1") (pin "P") (pinfunction "P_P") (pintype "bidirectional"))
      (node (ref "M2") (pin "P") (pinfunction "P_P") (pintype "bidirectional"))
      (node (ref "Q1") (pin "3") (pinfunction "D_3") (pintype "passive"))
    )
    (net (code "46") (name "VBUS") (class "Default")
      (node (ref "IC2") (pin "P$33") (pinfunction "IO19_P$33") (pintype "bidirectional"))
      (node (ref "IC4") (pin "8") (pinfunction "VBUS_8") (pintype "power_in"))
      (node (ref "R7") (pin "1") (pinfunction "1_1") (pintype "passive"))
      (node (ref "R8") (pin "2") (pinfunction "2_2") (pintype "passive"))
    )
    (net (code "47") (name "VIBRATE0") (class "Default")
      (node (ref "IC2") (pin "P$26") (pinfunction "IO20_P$26") (pintype "bidirectional"))
      (node (ref "Q4") (pin "2") (pinfunction "G_2") (pintype "passive"))
    )
    (net (code "48") (name "VIBRATE1") (class "Default")
      (node (ref "IC2") (pin "P$20") (pinfunction "IO13_P$20") (pintype "bidirectional"))
      (node (ref "Q4") (pin "5") (pinfunction "G_5") (pintype "passive"))
    )
    (net (code "49") (name "unconnected-(IC1-MISO-Pad7)") (class "Default")
      (node (ref "IC1") (pin "7") (pinfunction "MISO_7") (pintype "bidirectional"))
    )
    (net (code "50") (name "unconnected-(IC1-SS-Pad1)") (class "Default")
      (node (ref "IC1") (pin "1") (pinfunction "SS_1") (pintype "bidirectional"))
    )
    (net (code "51") (name "unconnected-(IC2-I34-PadP$9)") (class "Default")
      (node (ref "IC2") (pin "P$9") (pinfunction "I34_P$9") (pintype "bidirectional"))
    )
    (net (code "52") (name "unconnected-(IC2-IO2-PadP$22)") (class "Default")
      (node (ref "IC2") (pin "P$22") (pinfunction "IO2_P$22") (pintype "bidirectional"))
    )
    (net (code "53") (name "unconnected-(IC2-IO5-PadP$29)") (class "Default")
      (node (ref "IC2") (pin "P$29") (pinfunction "IO5_P$29") (pintype "bidirectional"))
    )
    (net (code "54") (name "unconnected-(IC2-IO7-PadP$27)") (class "Default")
      (node (ref "IC2") (pin "P$27") (pinfunction "IO7_P$27") (pintype "bidirectional"))
    )
    (net (code "55") (name "unconnected-(IC2-IO8-PadP$28)") (class "Default")
      (node (ref "IC2") (pin "P$28") (pinfunction "IO8_P$28") (pintype "bidirectional"))
    )
    (net (code "56") (name "unconnected-(IC2-IO12-PadP$19)") (class "Default")
      (node (ref "IC2") (pin "P$19") (pinfunction "IO12_P$19") (pintype "bidirectional"))
    )
    (net (code "57") (name "unconnected-(IC2-IO14-PadP$18)") (class "Default")
      (node (ref "IC2") (pin "P$18") (pinfunction "IO14_P$18") (pintype "bidirectional"))
    )
    (net (code "58") (name "unconnected-(IC2-IO15-PadP$21)") (class "Default")
      (node (ref "IC2") (pin "P$21") (pinfunction "IO15_P$21") (pintype "bidirectional"))
    )
    (net (code "59") (name "unconnected-(IC4-1_NC-Pad10)") (class "Default")
      (node (ref "IC4") (pin "10") (pinfunction "1_NC_10") (pintype "passive"))
    )
    (net (code "60") (name "unconnected-(IC4-2_NC-Pad16)") (class "Default")
      (node (ref "IC4") (pin "16") (pinfunction "2_NC_16") (pintype "passive"))
    )
    (net (code "61") (name "unconnected-(IC4-CTS-Pad18)") (class "Default")
      (node (ref "IC4") (pin "18") (pinfunction "CTS_18") (pintype "input"))
    )
    (net (code "62") (name "unconnected-(IC4-DCD-Pad24)") (class "Default")
      (node (ref "IC4") (pin "24") (pinfunction "DCD_24") (pintype "input"))
    )
    (net (code "63") (name "unconnected-(IC4-DSR-Pad22)") (class "Default")
      (node (ref "IC4") (pin "22") (pinfunction "DSR_22") (pintype "input"))
    )
    (net (code "64") (name "unconnected-(IC4-GPIO.0{slash}TXT-Pad14)") (class "Default")
      (node (ref "IC4") (pin "14") (pinfunction "GPIO.0/TXT_14") (pintype "bidirectional"))
    )
    (net (code "65") (name "unconnected-(IC4-GPIO.1{slash}RXT-Pad13)") (class "Default")
      (node (ref "IC4") (pin "13") (pinfunction "GPIO.1/RXT_13") (pintype "bidirectional"))
    )
    (net (code "66") (name "unconnected-(IC4-GPIO.2{slash}RS485-Pad12)") (class "Default")
      (node (ref "IC4") (pin "12") (pinfunction "GPIO.2/RS485_12") (pintype "bidirectional"))
    )
    (net (code "67") (name "unconnected-(IC4-GPIO.3{slash}WAKEUP-Pad11)") (class "Default")
      (node (ref "IC4") (pin "11") (pinfunction "GPIO.3/WAKEUP_11") (pintype "bidirectional"))
    )
    (net (code "68") (name "unconnected-(IC4-SUSPEND-Pad17)") (class "Default")
      (node (ref "IC4") (pin "17") (pinfunction "SUSPEND_17") (pintype "output"))
    )
    (net (code "69") (name "unconnected-(IC4-~{RI}{slash}CLK-Pad1)") (class "Default")
      (node (ref "IC4") (pin "1") (pinfunction "~{RI}/CLK_1") (pintype "bidirectional"))
    )
    (net (code "70") (name "unconnected-(IC4-~{SUSPEND}-Pad15)") (class "Default")
      (node (ref "IC4") (pin "15") (pinfunction "~{SUSPEND}_15") (pintype "output"))
    )
    (net (code "71") (name "unconnected-(IC8-OCS_AUX-Pad10)") (class "Default")
      (node (ref "IC8") (pin "10") (pinfunction "OCS_AUX_10") (pintype "bidirectional"))
    )
    (net (code "72") (name "unconnected-(IC8-SDO_AUX-Pad11)") (class "Default")
      (node (ref "IC8") (pin "11") (pinfunction "SDO_AUX_11") (pintype "bidirectional"))
    )
    (net (code "73") (name "unconnected-(J2-Pad4)") (class "Default")
      (node (ref "J2") (pin "4") (pinfunction "4_4") (pintype "passive"))
    )
    (net (code "74") (name "unconnected-(LED3-DO-PadDOUT)") (class "Default")
      (node (ref "LED3") (pin "DOUT") (pinfunction "DO_DOUT") (pintype "output"))
    )
  )
)
